# P4.net
KiCad netlist of a schematic drawn in Altium Designer
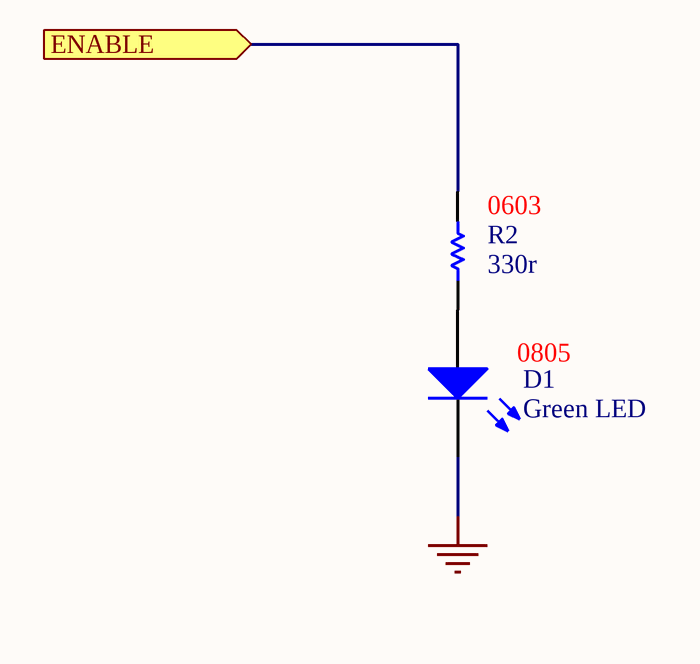
[diagram p0: P4.SchDoc]

(export (version "E")
  (design (tool "Eeschema 10.0.6"))
  (components
    (comp (ref "D1")
      (value "Green LED")
      (footprint "LED 0805N")
      (description "Typical INFRARED GaAs LED")
      (fields (field (name "PUBLISHER") "Altium Limited"))
      (libsource (lib "Miscellaneous Devices") (part "LED0"))
    )
    (comp (ref "R2")
      (value "330r")
      (footprint "RESC1608N")
      (description "Resistor")
      (fields (field (name "Comment") "Res1") (field (name "PUBLISHER") "Altium Limited"))
      (libsource (lib "Miscellaneous Devices") (part "Res1"))
    )
  )
  (nets
    (net (code "1") (name "/ENABLE") (class "Default")
      (node (ref "R2") (pin "2") (pinfunction "2_2") (pintype "passive"))
    )
    (net (code "2") (name "GND") (class "Default")
      (node (ref "D1") (pin "2") (pinfunction "K_2") (pintype "passive"))
    )
    (net (code "3") (name "Net-(D1-A)") (class "Default")
      (node (ref "D1") (pin "1") (pinfunction "A_1") (pintype "passive"))
      (node (ref "R2") (pin "1") (pinfunction "1_1") (pintype "passive"))
    )
  )
)
